# PB2_MFB_Butterworth.net
KiCad netlist of a schematic drawn in Altium Designer
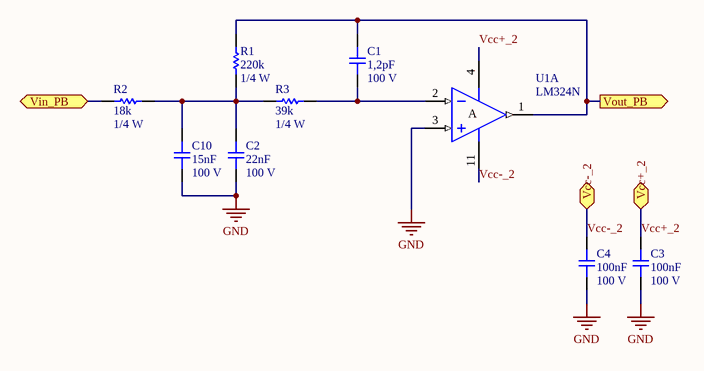
[diagram p0: PB2_MFB_Butterworth.SchDoc]

(export (version "E")
  (design (tool "Eeschema 10.0.6"))
  (components
    (comp (ref "C1")
      (value "1,2pF")
      (footprint "0805C")
      (description "Capacitor")
      (fields (field (name "VOLTAGE") "100 V") (field (name "PUBLISHER") "Altium Limited"))
      (libsource (lib "GPDSE") (part "Capacitor"))
    )
    (comp (ref "C2")
      (value "22nF")
      (footprint "0805C")
      (description "Capacitor")
      (fields (field (name "VOLTAGE") "100 V") (field (name "PUBLISHER") "Altium Limited"))
      (libsource (lib "GPDSE") (part "Capacitor"))
    )
    (comp (ref "C3")
      (value "100nF")
      (footprint "0805C")
      (description "Capacitor")
      (fields (field (name "VOLTAGE") "100 V") (field (name "PUBLISHER") "Altium Limited"))
      (libsource (lib "GPDSE") (part "Capacitor"))
    )
    (comp (ref "C4")
      (value "100nF")
      (footprint "0805C")
      (description "Capacitor")
      (fields (field (name "VOLTAGE") "100 V") (field (name "PUBLISHER") "Altium Limited"))
      (libsource (lib "GPDSE") (part "Capacitor"))
    )
    (comp (ref "C10")
      (value "15nF")
      (footprint "0805C")
      (description "Capacitor")
      (fields (field (name "VOLTAGE") "100 V") (field (name "PUBLISHER") "Altium Limited"))
      (libsource (lib "GPDSE") (part "Capacitor"))
    )
    (comp (ref "R1")
      (value "220k")
      (footprint "0805R")
      (description "Resistor")
      (fields
        (field (name "TOLERANCE") "5%")
        (field (name "POWER") "1/4 W")
        (field (name "PUBLISHER") "Altium Limited")
      )
      (libsource (lib "GPDSE") (part "Resistor"))
    )
    (comp (ref "R2")
      (value "18k")
      (footprint "0805R")
      (description "Resistor")
      (fields
        (field (name "TOLERANCE") "5%")
        (field (name "POWER") "1/4 W")
        (field (name "PUBLISHER") "Altium Limited")
      )
      (libsource (lib "GPDSE") (part "Resistor"))
    )
    (comp (ref "R3")
      (value "39k")
      (footprint "0805R")
      (description "Resistor")
      (fields
        (field (name "TOLERANCE") "5%")
        (field (name "POWER") "1/4 W")
        (field (name "PUBLISHER") "Altium Limited")
      )
      (libsource (lib "GPDSE") (part "Resistor"))
    )
    (comp (ref "U1")
      (value "LM324N")
      (footprint "N014")
      (description "Quadruple Operational Amplifier")
      (fields (field (name "PUBLISHER") "Altium Limited"))
      (libsource (lib "TI Operational Amplifier") (part "LM324N"))
    )
  )
  (nets
    (net (code "1") (name "/Vcc+_2") (class "Default")
      (node (ref "C3") (pin "2") (pinfunction "2_2") (pintype "passive"))
      (node (ref "U1") (pin "4") (pinfunction "V+_4") (pintype "power_in"))
    )
    (net (code "2") (name "/Vcc-_2") (class "Default")
      (node (ref "C4") (pin "2") (pinfunction "2_2") (pintype "passive"))
      (node (ref "U1") (pin "11") (pinfunction "V-_11") (pintype "power_in"))
    )
    (net (code "3") (name "/Vin_PB") (class "Default")
      (node (ref "R2") (pin "1") (pinfunction "1_1") (pintype "passive"))
    )
    (net (code "4") (name "/Vout_PB") (class "Default")
      (node (ref "C1") (pin "2") (pinfunction "2_2") (pintype "passive"))
      (node (ref "R1") (pin "2") (pinfunction "2_2") (pintype "passive"))
      (node (ref "U1") (pin "1") (pinfunction "OUT_1") (pintype "output"))
    )
    (net (code "5") (name "GND") (class "Default")
      (node (ref "C10") (pin "1") (pinfunction "1_1") (pintype "passive"))
      (node (ref "C2") (pin "1") (pinfunction "1_1") (pintype "passive"))
      (node (ref "C3") (pin "1") (pinfunction "1_1") (pintype "passive"))
      (node (ref "C4") (pin "1") (pinfunction "1_1") (pintype "passive"))
      (node (ref "U1") (pin "3") (pinfunction "IN+_3") (pintype "input"))
    )
    (net (code "6") (name "Net-(C10-Pad2)") (class "Default")
      (node (ref "C10") (pin "2") (pinfunction "2_2") (pintype "passive"))
      (node (ref "C2") (pin "2") (pinfunction "2_2") (pintype "passive"))
      (node (ref "R1") (pin "1") (pinfunction "1_1") (pintype "passive"))
      (node (ref "R2") (pin "2") (pinfunction "2_2") (pintype "passive"))
      (node (ref "R3") (pin "1") (pinfunction "1_1") (pintype "passive"))
    )
    (net (code "7") (name "Net-(U1A-IN-)") (class "Default")
      (node (ref "C1") (pin "1") (pinfunction "1_1") (pintype "passive"))
      (node (ref "R3") (pin "2") (pinfunction "2_2") (pintype "passive"))
      (node (ref "U1") (pin "2") (pinfunction "IN-_2") (pintype "input"))
    )
  )
)
